# Controller.net
KiCad netlist of a schematic drawn in Altium Designer
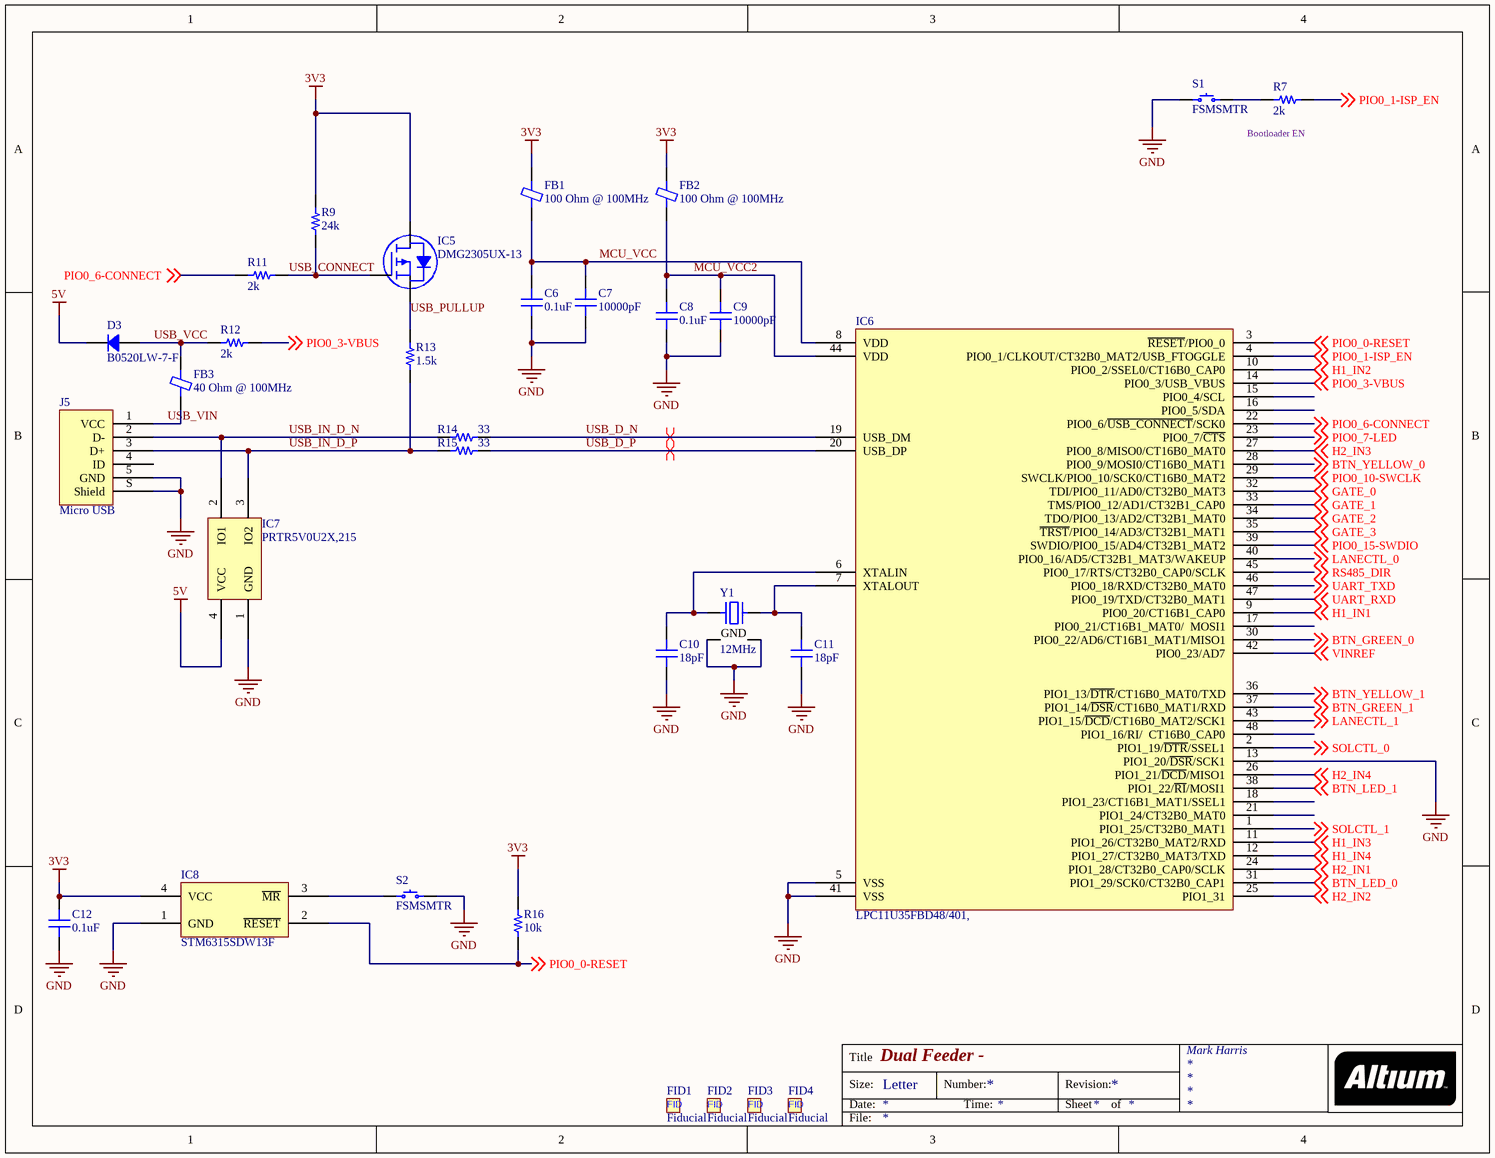
[diagram p0: Controller.SchDoc]

(export (version "E")
  (design (tool "Eeschema 10.0.6"))
  (components
    (comp (ref "C6")
      (value "0.1uF")
      (footprint "CAP 0603/1608")
      (description "CAP CER 0.1UF 50V X7R 0603")
      (fields
        (field (name "PART NUMBER") "CL10B104JB8NNNC")
        (field (name "MANUFACTURER") "Samsung Electro-Mechanics America, Inc.")
      )
      (libsource (lib "Celestial Library Database") (part "Capacitor"))
    )
    (comp (ref "C7")
      (value "10000pF")
      (footprint "CAP 0603/1608")
      (description "CAP CER 10000PF 50V X7R 0603")
      (fields
        (field (name "PART NUMBER") "CL10B103KB8NCNC")
        (field (name "MANUFACTURER") "Samsung Electro-Mechanics America, Inc.")
      )
      (libsource (lib "Celestial Library Database") (part "Capacitor"))
    )
    (comp (ref "C8")
      (value "0.1uF")
      (footprint "CAP 0603/1608")
      (description "CAP CER 0.1UF 50V X7R 0603")
      (fields
        (field (name "PART NUMBER") "CL10B104JB8NNNC")
        (field (name "MANUFACTURER") "Samsung Electro-Mechanics America, Inc.")
      )
      (libsource (lib "Celestial Library Database") (part "Capacitor"))
    )
    (comp (ref "C9")
      (value "10000pF")
      (footprint "CAP 0603/1608")
      (description "CAP CER 10000PF 50V X7R 0603")
      (fields
        (field (name "PART NUMBER") "CL10B103KB8NCNC")
        (field (name "MANUFACTURER") "Samsung Electro-Mechanics America, Inc.")
      )
      (libsource (lib "Celestial Library Database") (part "Capacitor"))
    )
    (comp (ref "C10")
      (value "18pF")
      (footprint "CAP 0603/1608")
      (description "CAP CER 18PF 50V NP0 0603")
      (fields (field (name "PART NUMBER") "C0603C180J5GACTU") (field (name "MANUFACTURER") "Kemet"))
      (libsource (lib "Celestial Library Database") (part "Capacitor"))
    )
    (comp (ref "C11")
      (value "18pF")
      (footprint "CAP 0603/1608")
      (description "CAP CER 18PF 50V NP0 0603")
      (fields (field (name "PART NUMBER") "C0603C180J5GACTU") (field (name "MANUFACTURER") "Kemet"))
      (libsource (lib "Celestial Library Database") (part "Capacitor"))
    )
    (comp (ref "C12")
      (value "0.1uF")
      (footprint "CAP 0603/1608")
      (description "CAP CER 0.1UF 50V X7R 0603")
      (fields
        (field (name "PART NUMBER") "CL10B104JB8NNNC")
        (field (name "MANUFACTURER") "Samsung Electro-Mechanics America, Inc.")
      )
      (libsource (lib "Celestial Library Database") (part "Capacitor"))
    )
    (comp (ref "D3")
      (value "B0520LW-7-F")
      (footprint "SOD-123")
      (description "DIODE SCHOTTKY 20V 500MA SOD123")
      (fields (field (name "MANUFACTURER") "Diodes Incorporated"))
      (libsource (lib "Celestial Library Database") (part "Diode"))
    )
    (comp (ref "FB1")
      (value "100 Ohm @ 100MHz")
      (footprint "FER 0603/1608")
      (description "FERRITE CHIP 100 OHM 0603")
      (fields (field (name "PART NUMBER") "BKP1608HS101-T") (field (name "MANUFACTURER") "Taiyo Yuden"))
      (libsource (lib "Celestial Library Database") (part "Ferrite Chip"))
    )
    (comp (ref "FB2")
      (value "100 Ohm @ 100MHz")
      (footprint "FER 0603/1608")
      (description "FERRITE CHIP 100 OHM 0603")
      (fields (field (name "PART NUMBER") "BKP1608HS101-T") (field (name "MANUFACTURER") "Taiyo Yuden"))
      (libsource (lib "Celestial Library Database") (part "Ferrite Chip"))
    )
    (comp (ref "FB3")
      (value "40 Ohm @ 100MHz")
      (footprint "FER 0805/2012")
      (description "FERRITE CHIP 40 OHM 0805")
      (fields (field (name "PART NUMBER") "MMZ2012S400AT000") (field (name "MANUFACTURER") "TDK Corporation"))
      (libsource (lib "Celestial Library Database") (part "Ferrite Chip"))
    )
    (comp (ref "FID1")
      (value "Fiducial")
      (footprint "Fiducial")
      (libsource (lib "Head Sensor") (part "Fiducial"))
    )
    (comp (ref "FID2")
      (value "Fiducial")
      (footprint "Fiducial")
      (libsource (lib "Head Sensor") (part "Fiducial"))
    )
    (comp (ref "FID3")
      (value "Fiducial")
      (footprint "Fiducial")
      (libsource (lib "Head Sensor") (part "Fiducial"))
    )
    (comp (ref "FID4")
      (value "Fiducial")
      (footprint "Fiducial")
      (libsource (lib "Head Sensor") (part "Fiducial"))
    )
    (comp (ref "IC5")
      (value "DMG2305UX-13")
      (footprint "DIODES SOT-23-3")
      (description "MOSFET P-CH 20V 4.2A SOT23")
      (fields (field (name "MANUFACTURER") "Diodes Incorporated"))
      (libsource (lib "Celestial Library Database") (part "DIODES MOSFET P-CH SOT-23-3"))
    )
    (comp (ref "IC6")
      (value "LPC11U35FBD48/401,")
      (footprint "NXP LQFP-48 7x7mm")
      (description "IC MCU ARM 64KB FLASH 48LQFP")
      (fields (field (name "MANUFACTURER") "NXP Semiconductors"))
      (libsource (lib "Celestial Library Database") (part "NXP LPC11U3X LQFP48"))
    )
    (comp (ref "IC7")
      (value "PRTR5V0U2X,215")
      (footprint "SOT143B")
      (description "TVS DIODE 5.5VWM SOT143B")
      (fields (field (name "MANUFACTURER") "NXP Semiconductors"))
      (libsource (lib "Celestial Library Database") (part "NXP PRTR5V0U2X"))
    )
    (comp (ref "IC8")
      (value "STM6315SDW13F")
      (footprint "ST SOT-143-4")
      (description "IC MPU RESET 2.93V 210MS SOT143-")
      (fields (field (name "MANUFACTURER") "STMicroelectronics"))
      (libsource (lib "Celestial Library Database") (part "ST STM3615"))
    )
    (comp (ref "J5")
      (value "Micro USB")
      (footprint "FCI USB 10118193-0001LF")
      (description "CONN USB MICRO B RECPT SMT R/A")
      (fields (field (name "PART NUMBER") "10118193-0001LF") (field (name "MANUFACTURER") "FCI"))
      (libsource (lib "Celestial Library Database") (part "USB 2.0 Type B Micro"))
    )
    (comp (ref "R7")
      (value "2k")
      (footprint "RES 0603/1608")
      (description "RES SMD 2K OHM 5% 1/10W 0603")
      (fields
        (field (name "PART NUMBER") "ERJ-3GEYJ202V")
        (field (name "MANUFACTURER") "Panasonic Electronic Components")
      )
      (libsource (lib "Celestial Library Database") (part "Resistor"))
    )
    (comp (ref "R9")
      (value "24k")
      (footprint "RES 0603/1608")
      (description "RES SMD 24K OHM 5% 1/10W 0603")
      (fields
        (field (name "PART NUMBER") "ERJ-3GEYJ243V")
        (field (name "MANUFACTURER") "Panasonic Electronic Components")
      )
      (libsource (lib "Celestial Library Database") (part "Resistor"))
    )
    (comp (ref "R11")
      (value "2k")
      (footprint "RES 0603/1608")
      (description "RES SMD 2K OHM 5% 1/10W 0603")
      (fields
        (field (name "PART NUMBER") "ERJ-3GEYJ202V")
        (field (name "MANUFACTURER") "Panasonic Electronic Components")
      )
      (libsource (lib "Celestial Library Database") (part "Resistor"))
    )
    (comp (ref "R12")
      (value "2k")
      (footprint "RES 0603/1608")
      (description "RES SMD 2K OHM 5% 1/10W 0603")
      (fields
        (field (name "PART NUMBER") "ERJ-3GEYJ202V")
        (field (name "MANUFACTURER") "Panasonic Electronic Components")
      )
      (libsource (lib "Celestial Library Database") (part "Resistor"))
    )
    (comp (ref "R13")
      (value "1.5k")
      (footprint "RES 0603/1608")
      (description "RES SMD 1.5K OHM 5% 1/10W 0603")
      (fields
        (field (name "PART NUMBER") "ERJ-3GEYJ152V")
        (field (name "MANUFACTURER") "Panasonic Electronic Components")
      )
      (libsource (lib "Celestial Library Database") (part "Resistor"))
    )
    (comp (ref "R14")
      (value "33")
      (footprint "RES 0603/1608")
      (description "RES SMD 33 OHM 1% 1/10W 0603")
      (fields
        (field (name "PART NUMBER") "ERJ-3EKF33R0V")
        (field (name "MANUFACTURER") "Panasonic Electronic Components")
      )
      (libsource (lib "Celestial Library Database") (part "Resistor"))
    )
    (comp (ref "R15")
      (value "33")
      (footprint "RES 0603/1608")
      (description "RES SMD 33 OHM 1% 1/10W 0603")
      (fields
        (field (name "PART NUMBER") "ERJ-3EKF33R0V")
        (field (name "MANUFACTURER") "Panasonic Electronic Components")
      )
      (libsource (lib "Celestial Library Database") (part "Resistor"))
    )
    (comp (ref "R16")
      (value "10k")
      (footprint "RES 0603/1608")
      (description "RES SMD 10K OHM 5% 1/10W 0603")
      (fields
        (field (name "PART NUMBER") "ERJ-3GEYJ103V")
        (field (name "MANUFACTURER") "Panasonic Electronic Components")
      )
      (libsource (lib "Celestial Library Database") (part "Resistor"))
    )
    (comp (ref "S1")
      (value "FSMSMTR")
      (footprint "TE FSMSMTR")
      (description "SWITCH TACTILE SPST-NO 0.05A 24V")
      (fields (field (name "MANUFACTURER") "TE Connectivity Alcoswitch Switches"))
      (libsource (lib "Celestial Library Database") (part "SPST-NO 2 PIN"))
    )
    (comp (ref "S2")
      (value "FSMSMTR")
      (footprint "TE FSMSMTR")
      (description "SWITCH TACTILE SPST-NO 0.05A 24V")
      (fields (field (name "MANUFACTURER") "TE Connectivity Alcoswitch Switches"))
      (libsource (lib "Celestial Library Database") (part "SPST-NO 2 PIN"))
    )
    (comp (ref "Y1")
      (value "12MHz")
      (footprint "ABRACON ABM8G")
      (description "CRYSTAL 12.0000MHZ 10PF SMD")
      (fields
        (field (name "PART NUMBER") "ABM8G-12.000MHZ-4Y-T3")
        (field (name "MANUFACTURER") "Abracon LLC")
      )
      (libsource (lib "Celestial Library Database") (part "Abracon Crystal ABM8G"))
    )
  )
  (nets
    (net (code "1") (name "/MCU_VCC") (class "Default")
      (node (ref "C6") (pin "1") (pinfunction "1_1") (pintype "passive"))
      (node (ref "C7") (pin "2") (pinfunction "2_2") (pintype "passive"))
      (node (ref "FB1") (pin "1") (pinfunction "1_1") (pintype "passive"))
      (node (ref "IC6") (pin "8") (pinfunction "VDD_8") (pintype "passive"))
    )
    (net (code "2") (name "/MCU_VCC2") (class "Default")
      (node (ref "C8") (pin "1") (pinfunction "1_1") (pintype "passive"))
      (node (ref "C9") (pin "2") (pinfunction "2_2") (pintype "passive"))
      (node (ref "FB2") (pin "1") (pinfunction "1_1") (pintype "passive"))
      (node (ref "IC6") (pin "44") (pinfunction "VDD_44") (pintype "passive"))
    )
    (net (code "3") (name "/USB_CONNECT") (class "Default")
      (node (ref "IC5") (pin "1") (pinfunction "G_1") (pintype "passive"))
      (node (ref "R11") (pin "2") (pinfunction "2_2") (pintype "passive"))
      (node (ref "R9") (pin "1") (pinfunction "1_1") (pintype "passive"))
    )
    (net (code "4") (name "/USB_D_N") (class "Default")
      (node (ref "IC6") (pin "19") (pinfunction "USB_DM_19") (pintype "passive"))
      (node (ref "R14") (pin "2") (pinfunction "2_2") (pintype "passive"))
    )
    (net (code "5") (name "/USB_D_P") (class "Default")
      (node (ref "IC6") (pin "20") (pinfunction "USB_DP_20") (pintype "passive"))
      (node (ref "R15") (pin "2") (pinfunction "2_2") (pintype "passive"))
    )
    (net (code "6") (name "/USB_IN_D_N") (class "Default")
      (node (ref "IC7") (pin "2") (pinfunction "IO1_2") (pintype "passive"))
      (node (ref "J5") (pin "2") (pinfunction "D-_2") (pintype "passive"))
      (node (ref "R14") (pin "1") (pinfunction "1_1") (pintype "passive"))
    )
    (net (code "7") (name "/USB_IN_D_P") (class "Default")
      (node (ref "IC7") (pin "3") (pinfunction "IO2_3") (pintype "passive"))
      (node (ref "J5") (pin "3") (pinfunction "D+_3") (pintype "passive"))
      (node (ref "R13") (pin "1") (pinfunction "1_1") (pintype "passive"))
      (node (ref "R15") (pin "1") (pinfunction "1_1") (pintype "passive"))
    )
    (net (code "8") (name "/USB_PULLUP") (class "Default")
      (node (ref "IC5") (pin "3") (pinfunction "S_3") (pintype "passive"))
      (node (ref "R13") (pin "2") (pinfunction "2_2") (pintype "passive"))
    )
    (net (code "9") (name "/USB_VCC") (class "Default")
      (node (ref "D3") (pin "1") (pinfunction "1_1") (pintype "passive"))
      (node (ref "FB3") (pin "2") (pinfunction "2_2") (pintype "passive"))
      (node (ref "R12") (pin "2") (pinfunction "2_2") (pintype "passive"))
    )
    (net (code "10") (name "/USB_VIN") (class "Default")
      (node (ref "FB3") (pin "1") (pinfunction "1_1") (pintype "passive"))
      (node (ref "J5") (pin "1") (pinfunction "VCC_1") (pintype "passive"))
    )
    (net (code "11") (name "3V3") (class "Default")
      (node (ref "C12") (pin "1") (pinfunction "1_1") (pintype "passive"))
      (node (ref "FB1") (pin "2") (pinfunction "2_2") (pintype "passive"))
      (node (ref "FB2") (pin "2") (pinfunction "2_2") (pintype "passive"))
      (node (ref "IC5") (pin "2") (pinfunction "D_2") (pintype "passive"))
      (node (ref "IC8") (pin "4") (pinfunction "VCC_4") (pintype "passive"))
      (node (ref "R16") (pin "2") (pinfunction "2_2") (pintype "passive"))
      (node (ref "R9") (pin "2") (pinfunction "2_2") (pintype "passive"))
    )
    (net (code "12") (name "5V") (class "Default")
      (node (ref "D3") (pin "2") (pinfunction "2_2") (pintype "passive"))
      (node (ref "IC7") (pin "4") (pinfunction "VCC_4") (pintype "passive"))
    )
    (net (code "13") (name "BTN_GREEN_0") (class "Default")
      (node (ref "IC6") (pin "30") (pinfunction "PIO0_22/AD6/CT16B1_MAT1/MISO1_30") (pintype "passive"))
    )
    (net (code "14") (name "BTN_GREEN_1") (class "Default")
      (node (ref "IC6") (pin "37") (pinfunction "PIO1_14/~{DSR}/CT16B0_MAT1/RXD_37") (pintype "passive"))
    )
    (net (code "15") (name "BTN_LED_0") (class "Default")
      (node (ref "IC6") (pin "31") (pinfunction "PIO1_29/SCK0/CT32B0_CAP1_31") (pintype "passive"))
    )
    (net (code "16") (name "BTN_LED_1") (class "Default")
      (node (ref "IC6") (pin "38") (pinfunction "PIO1_22/~{RI}/MOSI1_38") (pintype "passive"))
    )
    (net (code "17") (name "BTN_YELLOW_0") (class "Default")
      (node (ref "IC6") (pin "28") (pinfunction "PIO0_9/MOSI0/CT16B0_MAT1_28") (pintype "passive"))
    )
    (net (code "18") (name "BTN_YELLOW_1") (class "Default")
      (node (ref "IC6") (pin "36") (pinfunction "PIO1_13/~{DTR}/CT16B0_MAT0/TXD_36") (pintype "passive"))
    )
    (net (code "19") (name "GATE_0") (class "Default")
      (node (ref "IC6") (pin "32") (pinfunction "TDI/PIO0_11/AD0/CT32B0_MAT3_32") (pintype "passive"))
    )
    (net (code "20") (name "GATE_1") (class "Default")
      (node (ref "IC6") (pin "33") (pinfunction "TMS/PIO0_12/AD1/CT32B1_CAP0_33") (pintype "passive"))
    )
    (net (code "21") (name "GATE_2") (class "Default")
      (node (ref "IC6") (pin "34") (pinfunction "TDO/PIO0_13/AD2/CT32B1_MAT0_34") (pintype "passive"))
    )
    (net (code "22") (name "GATE_3") (class "Default")
      (node (ref "IC6") (pin "35") (pinfunction "~{TRST}/PIO0_14/AD3/CT32B1_MAT1_35") (pintype "passive"))
    )
    (net (code "23") (name "GND") (class "Default")
      (node (ref "C10") (pin "1") (pinfunction "1_1") (pintype "passive"))
      (node (ref "C11") (pin "1") (pinfunction "1_1") (pintype "passive"))
      (node (ref "C12") (pin "2") (pinfunction "2_2") (pintype "passive"))
      (node (ref "C6") (pin "2") (pinfunction "2_2") (pintype "passive"))
      (node (ref "C7") (pin "1") (pinfunction "1_1") (pintype "passive"))
      (node (ref "C8") (pin "2") (pinfunction "2_2") (pintype "passive"))
      (node (ref "C9") (pin "1") (pinfunction "1_1") (pintype "passive"))
      (node (ref "IC6") (pin "13") (pinfunction "PIO1_20/~{DSR}/SCK1_13") (pintype "passive"))
      (node (ref "IC6") (pin "41") (pinfunction "VSS_41") (pintype "passive"))
      (node (ref "IC6") (pin "5") (pinfunction "VSS_5") (pintype "passive"))
      (node (ref "IC7") (pin "1") (pinfunction "GND_1") (pintype "passive"))
      (node (ref "IC8") (pin "1") (pinfunction "GND_1") (pintype "passive"))
      (node (ref "J5") (pin "5") (pinfunction "GND_5") (pintype "passive"))
      (node (ref "J5") (pin "S") (pinfunction "Shield_S") (pintype "passive"))
      (node (ref "S1") (pin "1") (pinfunction "1_1") (pintype "passive"))
      (node (ref "S2") (pin "2") (pinfunction "2_2") (pintype "passive"))
      (node (ref "Y1") (pin "2") (pinfunction "GND_2") (pintype "passive"))
      (node (ref "Y1") (pin "4") (pinfunction "GND_4") (pintype "passive"))
    )
    (net (code "24") (name "H1_IN1") (class "Default")
      (node (ref "IC6") (pin "9") (pinfunction "PIO0_20/CT16B1_CAP0_9") (pintype "passive"))
    )
    (net (code "25") (name "H1_IN2") (class "Default")
      (node (ref "IC6") (pin "10") (pinfunction "PIO0_2/SSEL0/CT16B0_CAP0_10") (pintype "passive"))
    )
    (net (code "26") (name "H1_IN3") (class "Default")
      (node (ref "IC6") (pin "11") (pinfunction "PIO1_26/CT32B0_MAT2/RXD_11") (pintype "passive"))
    )
    (net (code "27") (name "H1_IN4") (class "Default")
      (node (ref "IC6") (pin "12") (pinfunction "PIO1_27/CT32B0_MAT3/TXD_12") (pintype "passive"))
    )
    (net (code "28") (name "H2_IN1") (class "Default")
      (node (ref "IC6") (pin "24") (pinfunction "PIO1_28/CT32B0_CAP0/SCLK_24") (pintype "passive"))
    )
    (net (code "29") (name "H2_IN2") (class "Default")
      (node (ref "IC6") (pin "25") (pinfunction "PIO1_31_25") (pintype "passive"))
    )
    (net (code "30") (name "H2_IN3") (class "Default")
      (node (ref "IC6") (pin "27") (pinfunction "PIO0_8/MISO0/CT16B0_MAT0_27") (pintype "passive"))
    )
    (net (code "31") (name "H2_IN4") (class "Default")
      (node (ref "IC6") (pin "26") (pinfunction "PIO1_21/~{DCD}/MISO1_26") (pintype "passive"))
    )
    (net (code "32") (name "LANECTL_0") (class "Default")
      (node (ref "IC6") (pin "40") (pinfunction "PIO0_16/AD5/CT32B1_MAT3/WAKEUP_40") (pintype "passive"))
    )
    (net (code "33") (name "LANECTL_1") (class "Default")
      (node (ref "IC6") (pin "43") (pinfunction "PIO1_15/~{DCD}/CT16B0_MAT2/SCK1_43") (pintype "passive"))
    )
    (net (code "34") (name "Net-(IC6-XTALIN)") (class "Default")
      (node (ref "C10") (pin "2") (pinfunction "2_2") (pintype "passive"))
      (node (ref "IC6") (pin "6") (pinfunction "XTALIN_6") (pintype "passive"))
      (node (ref "Y1") (pin "1") (pinfunction "1_1") (pintype "passive"))
    )
    (net (code "35") (name "Net-(IC6-XTALOUT)") (class "Default")
      (node (ref "C11") (pin "2") (pinfunction "2_2") (pintype "passive"))
      (node (ref "IC6") (pin "7") (pinfunction "XTALOUT_7") (pintype "passive"))
      (node (ref "Y1") (pin "3") (pinfunction "3_3") (pintype "passive"))
    )
    (net (code "36") (name "Net-(IC8-~{MR})") (class "Default")
      (node (ref "IC8") (pin "3") (pinfunction "~{MR}_3") (pintype "passive"))
      (node (ref "S2") (pin "1") (pinfunction "1_1") (pintype "passive"))
    )
    (net (code "37") (name "Net-(R7-Pad2)") (class "Default")
      (node (ref "R7") (pin "2") (pinfunction "2_2") (pintype "passive"))
      (node (ref "S1") (pin "2") (pinfunction "2_2") (pintype "passive"))
    )
    (net (code "38") (name "PIO0_0-RESET") (class "Default")
      (node (ref "IC6") (pin "3") (pinfunction "~{RESET}/PIO0_0_3") (pintype "passive"))
      (node (ref "IC8") (pin "2") (pinfunction "~{RESET}_2") (pintype "passive"))
      (node (ref "R16") (pin "1") (pinfunction "1_1") (pintype "passive"))
    )
    (net (code "39") (name "PIO0_1-ISP_EN") (class "Default")
      (node (ref "IC6") (pin "4") (pinfunction "PIO0_1/CLKOUT/CT32B0_MAT2/USB_FTOGGLE_4") (pintype "passive"))
      (node (ref "R7") (pin "1") (pinfunction "1_1") (pintype "passive"))
    )
    (net (code "40") (name "PIO0_3-VBUS") (class "Default")
      (node (ref "IC6") (pin "14") (pinfunction "PIO0_3/USB_VBUS_14") (pintype "passive"))
      (node (ref "R12") (pin "1") (pinfunction "1_1") (pintype "passive"))
    )
    (net (code "41") (name "PIO0_6-CONNECT") (class "Default")
      (node (ref "IC6") (pin "22") (pinfunction "PIO0_6/~{USB_CONNECT}/SCK0_22") (pintype "passive"))
      (node (ref "R11") (pin "1") (pinfunction "1_1") (pintype "passive"))
    )
    (net (code "42") (name "PIO0_7-LED") (class "Default")
      (node (ref "IC6") (pin "23") (pinfunction "PIO0_7/~{CTS}_23") (pintype "passive"))
    )
    (net (code "43") (name "PIO0_10-SWCLK") (class "Default")
      (node (ref "IC6") (pin "29") (pinfunction "SWCLK/PIO0_10/SCK0/CT16B0_MAT2_29") (pintype "passive"))
    )
    (net (code "44") (name "PIO0_15-SWDIO") (class "Default")
      (node (ref "IC6") (pin "39") (pinfunction "SWDIO/PIO0_15/AD4/CT32B1_MAT2_39") (pintype "passive"))
    )
    (net (code "45") (name "RS485_DIR") (class "Default")
      (node (ref "IC6") (pin "45") (pinfunction "PIO0_17/RTS/CT32B0_CAP0/SCLK_45") (pintype "passive"))
    )
    (net (code "46") (name "SOLCTL_0") (class "Default")
      (node (ref "IC6") (pin "2") (pinfunction "PIO1_19/~{DTR}/SSEL1_2") (pintype "passive"))
    )
    (net (code "47") (name "SOLCTL_1") (class "Default")
      (node (ref "IC6") (pin "1") (pinfunction "PIO1_25/CT32B0_MAT1_1") (pintype "passive"))
    )
    (net (code "48") (name "UART_RXD") (class "Default")
      (node (ref "IC6") (pin "47") (pinfunction "PIO0_19/TXD/CT32B0_MAT1_47") (pintype "passive"))
    )
    (net (code "49") (name "UART_TXD") (class "Default")
      (node (ref "IC6") (pin "46") (pinfunction "PIO0_18/RXD/CT32B0_MAT0_46") (pintype "passive"))
    )
    (net (code "50") (name "VINREF") (class "Default")
      (node (ref "IC6") (pin "42") (pinfunction "PIO0_23/AD7_42") (pintype "passive"))
    )
    (net (code "51") (name "unconnected-(IC6-PIO0_4{slash}SCL-Pad15)") (class "Default")
      (node (ref "IC6") (pin "15") (pinfunction "PIO0_4/SCL_15") (pintype "passive"))
    )
    (net (code "52") (name "unconnected-(IC6-PIO0_5{slash}SDA-Pad16)") (class "Default")
      (node (ref "IC6") (pin "16") (pinfunction "PIO0_5/SDA_16") (pintype "passive"))
    )
    (net (code "53") (name "unconnected-(IC6-PIO0_21{slash}CT16B1_MAT0{slash}__MOSI1-Pad17)") (class "Default")
      (node (ref "IC6") (pin "17") (pinfunction "PIO0_21/CT16B1_MAT0/__MOSI1_17") (pintype "passive"))
    )
    (net (code "54") (name "unconnected-(IC6-PIO1_16{slash}RI{slash}__CT16B0_CAP0-Pad48)") (class "Default")
      (node (ref "IC6") (pin "48") (pinfunction "PIO1_16/RI/__CT16B0_CAP0_48") (pintype "passive"))
    )
    (net (code "55") (name "unconnected-(IC6-PIO1_23{slash}CT16B1_MAT1{slash}SSEL1-Pad18)") (class "Default")
      (node (ref "IC6") (pin "18") (pinfunction "PIO1_23/CT16B1_MAT1/SSEL1_18") (pintype "passive"))
    )
    (net (code "56") (name "unconnected-(IC6-PIO1_24{slash}CT32B0_MAT0-Pad21)") (class "Default")
      (node (ref "IC6") (pin "21") (pinfunction "PIO1_24/CT32B0_MAT0_21") (pintype "passive"))
    )
    (net (code "57") (name "unconnected-(J5-ID-Pad4)") (class "Default")
      (node (ref "J5") (pin "4") (pinfunction "ID_4") (pintype "passive"))
    )
  )
)
